# Hydrogen_Sensor.net
KiCad netlist of a schematic drawn in Altium Designer
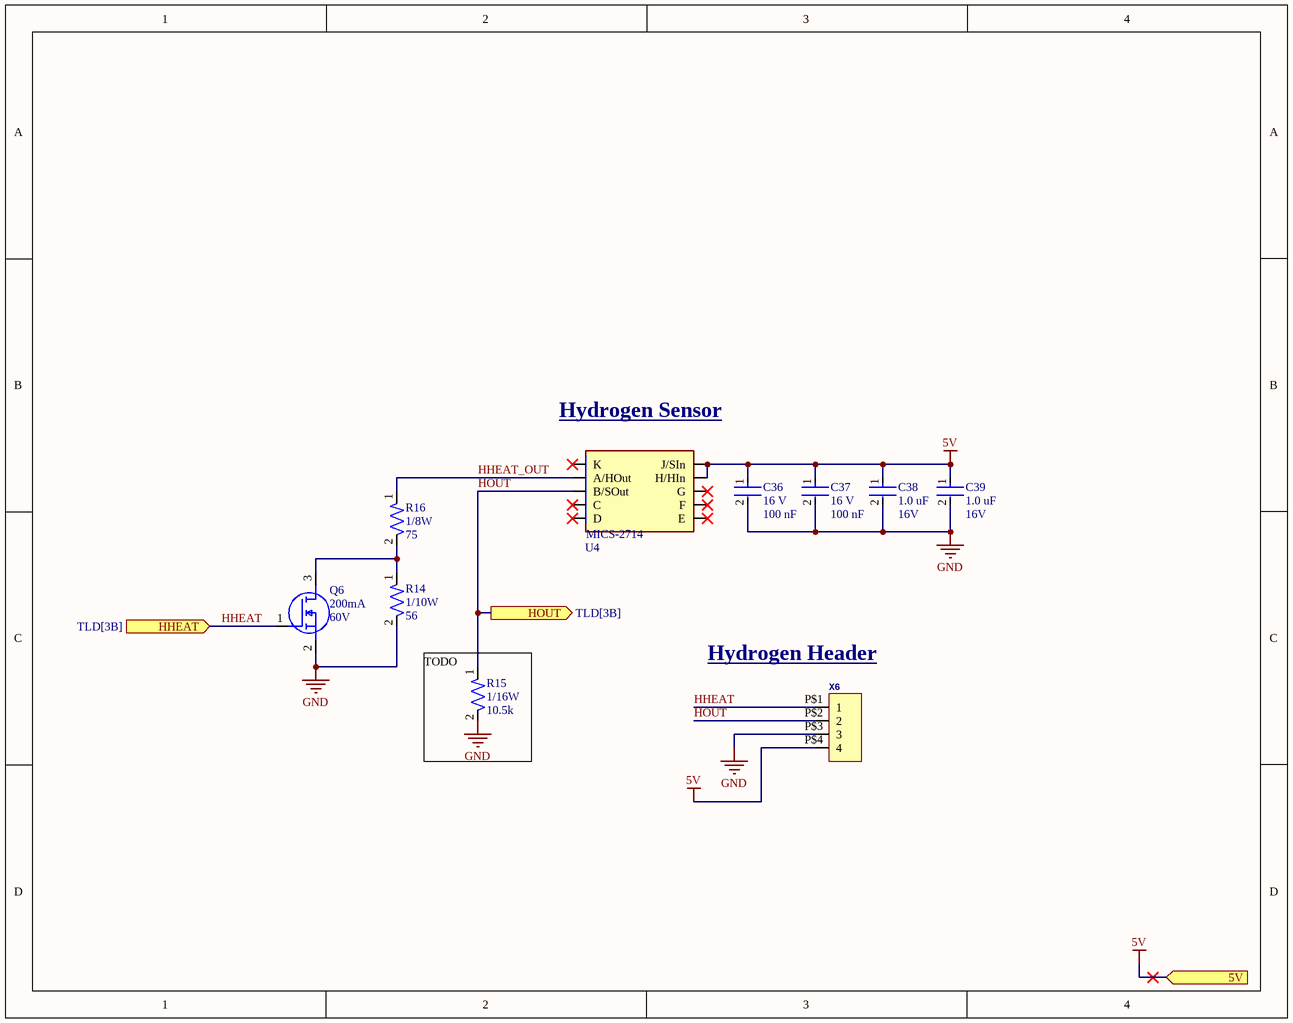
[diagram p0: Hydrogen_Sensor.SchDoc]

(export (version "E")
  (design (tool "Eeschema 10.0.6"))
  (components
    (comp (ref "C36")
      (value "CC0402KRX7R7BB104")
      (footprint "CAP-0402")
      (description "CAP CER 0.1UF 16V X7R 0402")
      (fields (field (name "VOLTAGE RATING") "16 V") (field (name "CAPACITANCE") "100 nF"))
      (libsource (lib "JLC_25") (part "CAP-0.1U-0001"))
    )
    (comp (ref "C37")
      (value "CC0402KRX7R7BB104")
      (footprint "CAP-0402")
      (description "CAP CER 0.1UF 16V X7R 0402")
      (fields (field (name "VOLTAGE RATING") "16 V") (field (name "CAPACITANCE") "100 nF"))
      (libsource (lib "JLC_25") (part "CAP-0.1U-0001"))
    )
    (comp (ref "C38")
      (value "CC0603KRX7R7BB105")
      (footprint "CAP-0603")
      (description "CAP CER 1UF 16V X7R 0603")
      (fields (field (name "CAPACITANCE") "1.0 uF") (field (name "VOLTAGE") "16V"))
      (libsource (lib "JLC_25") (part "CAP-1U-0002"))
    )
    (comp (ref "C39")
      (value "CC0603KRX7R7BB105")
      (footprint "CAP-0603")
      (description "CAP CER 1UF 16V X7R 0603")
      (fields (field (name "CAPACITANCE") "1.0 uF") (field (name "VOLTAGE") "16V"))
      (libsource (lib "JLC_25") (part "CAP-1U-0002"))
    )
    (comp (ref "Q6")
      (value "T2N7002AK,LM")
      (footprint "NMOS-SOT23-3")
      (description "MOSFET N-CH 60V 200MA SOT23")
      (fields
        (field (name "MANUFACTURER") "Toshiba")
        (field (name "ID-CONTINUOUS") "200mA")
        (field (name "VDS-MAX") "60V")
      )
      (libsource (lib "MasterLib") (part "NMOS-200MA-0001"))
    )
    (comp (ref "R14")
      (value "RC0603FR-0756RL")
      (footprint "RC0603N_YAG")
      (description "56 Ohms ±1% 0.1W, 1/10W Chip Resistor 0603 (1608 Metric) Moisture Resistant Thick Film")
      (fields
        (field (name "POWER") "1/10W")
        (field (name "RESISTANCE") "56")
        (field (name "COPYRIGHT") "Copyright (C) 2025 Ultra Librarian. All rights reserved.")
      )
      (libsource (lib "JLC_25") (part "RES-56-0001"))
    )
    (comp (ref "R15")
      (value "RC0402FR-0710K5L")
      (footprint "RES-0402")
      (description "RES 10.5K OHM 1% 1/16W 0402")
      (fields
        (field (name "TOLERANCE") "1%")
        (field (name "POWER") "1/16W")
        (field (name "RESISTANCE") "10.5k")
      )
      (libsource (lib "JLC_25") (part "RES-10.5k-0001"))
    )
    (comp (ref "R16")
      (value "CRCW060375R0FKEA")
      (footprint "RESC1508X50N")
      (description "75 Ohms Â±1% 0.1W, 1/10W Chip Resistor 0603 _1608 Metric_ Automotive AEC-Q200 Thick Film")
      (fields
        (field (name "MF") "Vishay Dale")
        (field (name "DIGI-KEY_PART_NUMBER") "541-75.0HCT-ND")
        (field (name "POWER") "1/8W")
        (field (name "RESISTANCE") "75")
      )
      (libsource (lib "JLC_25") (part "RES-75-0001"))
    )
    (comp (ref "U4")
      (value "MICS-2714")
      (footprint "MICS-SMD10")
      (description "MiCS-2714 Nitrogen Dioxide (NO2) Sensor mikroBUSâ„¢ Clickâ„¢ Platform Evaluation Expansion Board")
      (fields (field (name "MF") "SGX Sensortech"))
      (libsource (lib "JLC_25") (part "IC-Hydrogen"))
    )
    (comp (ref "X6")
      (value "Molex - Micro-Fit 3.0 Series connector,  3.00mm (0.118\") pitch header, 4 positions.")
      (footprint "43045-0400")
      (libsource (lib "Molex Microfit") (part "HEADER_POS4_?43045-0401"))
    )
  )
  (nets
    (net (code "1") (name "/HHEAT") (class "Default")
      (node (ref "Q6") (pin "1") (pinfunction "G_1") (pintype "passive"))
      (node (ref "X6") (pin "P$1") (pinfunction "1_P$1") (pintype "passive"))
    )
    (net (code "2") (name "/HHEAT_OUT") (class "Default")
      (node (ref "R16") (pin "1") (pinfunction "1_1") (pintype "passive"))
      (node (ref "U4") (pin "A") (pinfunction "A/HOut_A") (pintype "bidirectional"))
    )
    (net (code "3") (name "/HOUT") (class "Default")
      (node (ref "R15") (pin "1") (pinfunction "1_1") (pintype "passive"))
      (node (ref "U4") (pin "B") (pinfunction "B/SOut_B") (pintype "bidirectional"))
      (node (ref "X6") (pin "P$2") (pinfunction "2_P$2") (pintype "passive"))
    )
    (net (code "4") (name "5V") (class "Default")
      (node (ref "C36") (pin "1") (pinfunction "1_1") (pintype "passive"))
      (node (ref "C37") (pin "1") (pinfunction "1_1") (pintype "passive"))
      (node (ref "C38") (pin "1") (pinfunction "1_1") (pintype "passive"))
      (node (ref "C39") (pin "1") (pinfunction "1_1") (pintype "passive"))
      (node (ref "U4") (pin "H") (pinfunction "H/HIn_H") (pintype "bidirectional"))
      (node (ref "U4") (pin "J") (pinfunction "J/SIn_J") (pintype "bidirectional"))
      (node (ref "X6") (pin "P$4") (pinfunction "4_P$4") (pintype "passive"))
    )
    (net (code "5") (name "GND") (class "Default")
      (node (ref "C36") (pin "2") (pinfunction "2_2") (pintype "passive"))
      (node (ref "C37") (pin "2") (pinfunction "2_2") (pintype "passive"))
      (node (ref "C38") (pin "2") (pinfunction "2_2") (pintype "passive"))
      (node (ref "C39") (pin "2") (pinfunction "2_2") (pintype "passive"))
      (node (ref "Q6") (pin "2") (pinfunction "S_2") (pintype "passive"))
      (node (ref "R14") (pin "2") (pinfunction "2_2") (pintype "passive"))
      (node (ref "R15") (pin "2") (pinfunction "2_2") (pintype "passive"))
      (node (ref "X6") (pin "P$3") (pinfunction "3_P$3") (pintype "passive"))
    )
    (net (code "6") (name "Net-(Q6-D)") (class "Default")
      (node (ref "Q6") (pin "3") (pinfunction "D_3") (pintype "passive"))
      (node (ref "R14") (pin "1") (pinfunction "1_1") (pintype "passive"))
      (node (ref "R16") (pin "2") (pinfunction "2_2") (pintype "passive"))
    )
    (net (code "7") (name "unconnected-(U4-PadC)") (class "Default")
      (node (ref "U4") (pin "C") (pinfunction "C_C") (pintype "bidirectional+no_connect"))
    )
    (net (code "8") (name "unconnected-(U4-PadD)") (class "Default")
      (node (ref "U4") (pin "D") (pinfunction "D_D") (pintype "bidirectional+no_connect"))
    )
    (net (code "9") (name "unconnected-(U4-PadE)") (class "Default")
      (node (ref "U4") (pin "E") (pinfunction "E_E") (pintype "bidirectional+no_connect"))
    )
    (net (code "10") (name "unconnected-(U4-PadF)") (class "Default")
      (node (ref "U4") (pin "F") (pinfunction "F_F") (pintype "bidirectional+no_connect"))
    )
    (net (code "11") (name "unconnected-(U4-PadG)") (class "Default")
      (node (ref "U4") (pin "G") (pinfunction "G_G") (pintype "bidirectional+no_connect"))
    )
    (net (code "12") (name "unconnected-(U4-PadK)") (class "Default")
      (node (ref "U4") (pin "K") (pinfunction "K_K") (pintype "bidirectional+no_connect"))
    )
  )
)
